# 07-AUDIO_INNER.net
KiCad netlist of a schematic drawn in Altium Designer
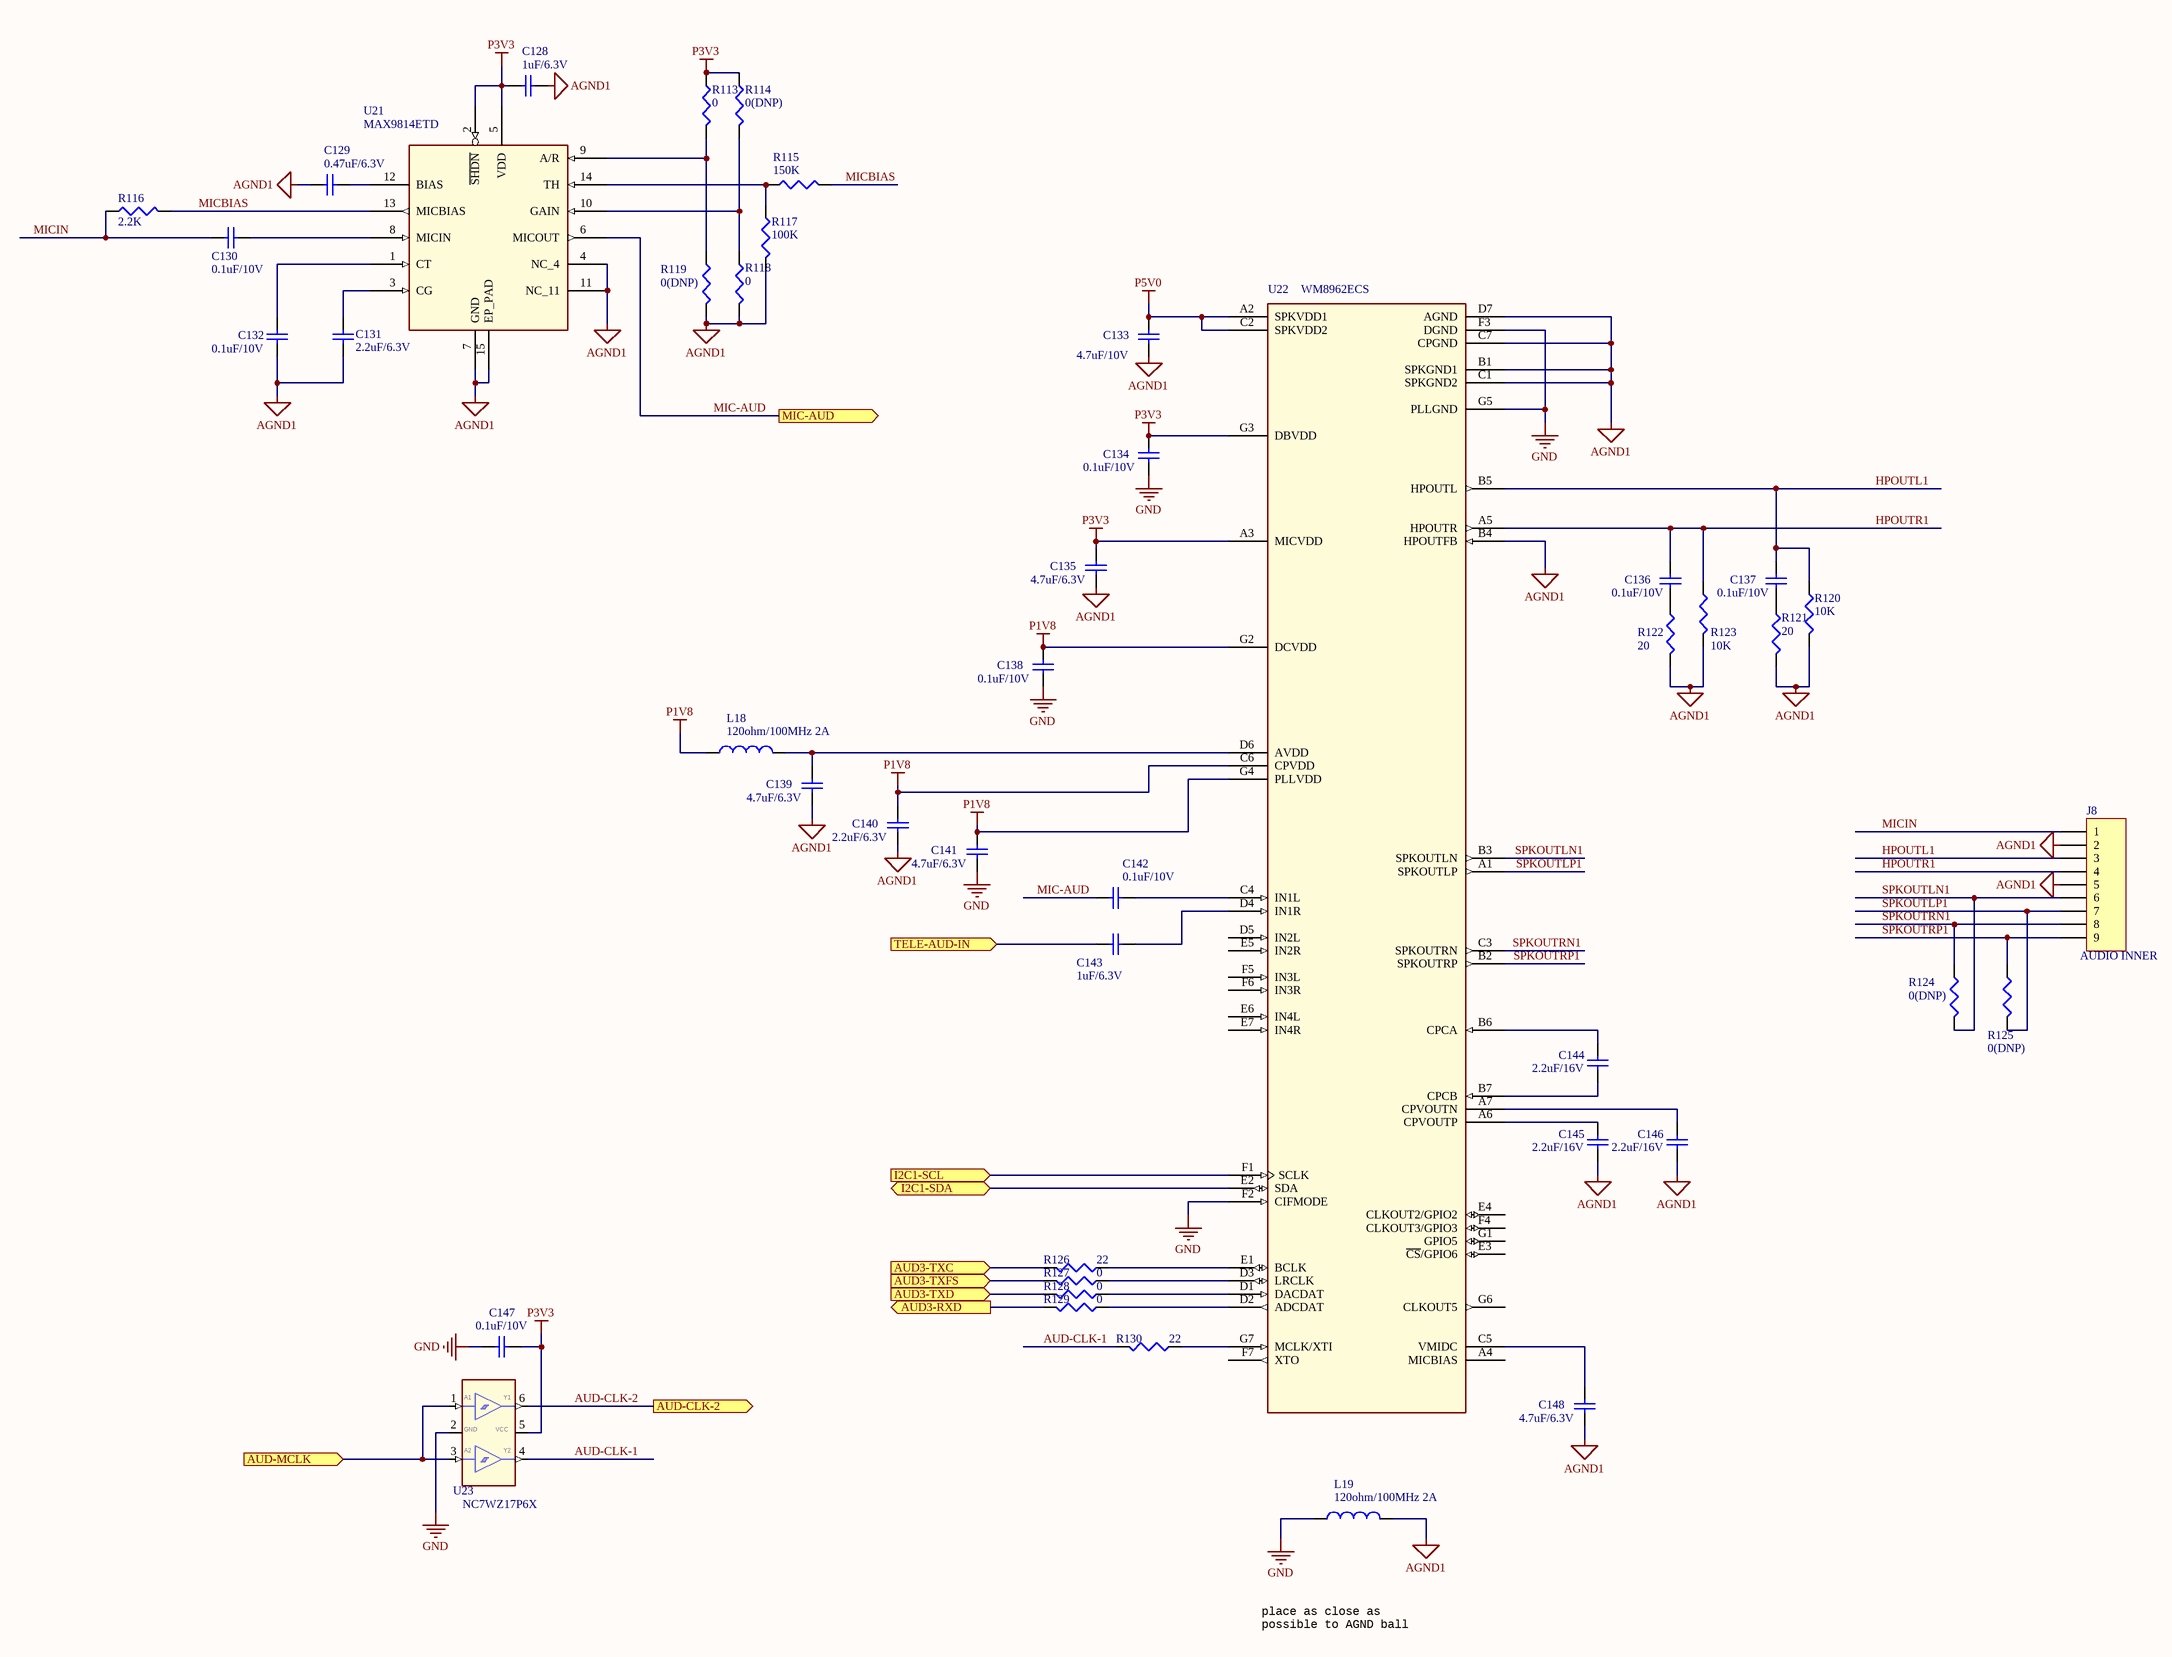
[diagram p0: 07-AUDIO_INNER.SchDoc]

(export (version "E")
  (design (tool "Eeschema 10.0.6"))
  (components
    (comp (ref "C128")
      (value "1uF/6.3V")
      (footprint "0402")
      (description "Capacitor")
      (fields (field (name "PUBLISHER") "Altium Limited"))
      (libsource (lib "Miscellaneous Devices") (part "Cap"))
    )
    (comp (ref "C129")
      (value "0.47uF/6.3V")
      (footprint "0402")
      (description "Capacitor")
      (fields (field (name "PUBLISHER") "Altium Limited"))
      (libsource (lib "Miscellaneous Devices") (part "Cap"))
    )
    (comp (ref "C130")
      (value "0.1uF/10V")
      (footprint "0402")
      (description "Capacitor")
      (fields (field (name "PUBLISHER") "Altium Limited"))
      (libsource (lib "Miscellaneous Devices") (part "Cap"))
    )
    (comp (ref "C131")
      (value "2.2uF/6.3V")
      (footprint "0603")
      (description "Capacitor")
      (fields (field (name "PUBLISHER") "Altium Limited"))
      (libsource (lib "Miscellaneous Devices") (part "Cap"))
    )
    (comp (ref "C132")
      (value "0.1uF/10V")
      (footprint "0402")
      (description "Capacitor")
      (fields (field (name "PUBLISHER") "Altium Limited"))
      (libsource (lib "Miscellaneous Devices") (part "Cap"))
    )
    (comp (ref "C133")
      (value "4.7uF/10V")
      (footprint "0805")
      (description "Capacitor")
      (fields (field (name "PUBLISHER") "Altium Limited"))
      (libsource (lib "Miscellaneous Devices") (part "Cap"))
    )
    (comp (ref "C134")
      (value "0.1uF/10V")
      (footprint "0402")
      (description "Capacitor")
      (fields (field (name "PUBLISHER") "Altium Limited"))
      (libsource (lib "Miscellaneous Devices") (part "Cap"))
    )
    (comp (ref "C135")
      (value "4.7uF/6.3V")
      (footprint "0603")
      (description "Capacitor")
      (fields (field (name "PUBLISHER") "Altium Limited"))
      (libsource (lib "Miscellaneous Devices") (part "Cap"))
    )
    (comp (ref "C136")
      (value "0.1uF/10V")
      (footprint "0402")
      (description "Capacitor")
      (fields (field (name "PUBLISHER") "Altium Limited"))
      (libsource (lib "Miscellaneous Devices") (part "Cap"))
    )
    (comp (ref "C137")
      (value "0.1uF/10V")
      (footprint "0402")
      (description "Capacitor")
      (fields (field (name "PUBLISHER") "Altium Limited"))
      (libsource (lib "Miscellaneous Devices") (part "Cap"))
    )
    (comp (ref "C138")
      (value "0.1uF/10V")
      (footprint "0402")
      (description "Capacitor")
      (fields (field (name "PUBLISHER") "Altium Limited"))
      (libsource (lib "Miscellaneous Devices") (part "Cap"))
    )
    (comp (ref "C139")
      (value "4.7uF/6.3V")
      (footprint "0603")
      (description "Capacitor")
      (fields (field (name "PUBLISHER") "Altium Limited"))
      (libsource (lib "Miscellaneous Devices") (part "Cap"))
    )
    (comp (ref "C140")
      (value "2.2uF/6.3V")
      (footprint "0603")
      (description "Capacitor")
      (fields (field (name "PUBLISHER") "Altium Limited"))
      (libsource (lib "Miscellaneous Devices") (part "Cap"))
    )
    (comp (ref "C141")
      (value "4.7uF/6.3V")
      (footprint "0603")
      (description "Capacitor")
      (fields (field (name "PUBLISHER") "Altium Limited"))
      (libsource (lib "Miscellaneous Devices") (part "Cap"))
    )
    (comp (ref "C142")
      (value "0.1uF/10V")
      (footprint "0402")
      (description "Capacitor")
      (fields (field (name "PUBLISHER") "Altium Limited"))
      (libsource (lib "Miscellaneous Devices") (part "Cap"))
    )
    (comp (ref "C143")
      (value "1uF/6.3V")
      (footprint "0402")
      (description "Capacitor")
      (fields (field (name "PUBLISHER") "Altium Limited"))
      (libsource (lib "Miscellaneous Devices") (part "Cap"))
    )
    (comp (ref "C144")
      (value "2.2uF/16V")
      (footprint "0603")
      (description "Capacitor")
      (fields (field (name "PUBLISHER") "Altium Limited"))
      (libsource (lib "Miscellaneous Devices") (part "Cap"))
    )
    (comp (ref "C145")
      (value "2.2uF/16V")
      (footprint "0603")
      (description "Capacitor")
      (fields (field (name "PUBLISHER") "Altium Limited"))
      (libsource (lib "Miscellaneous Devices") (part "Cap"))
    )
    (comp (ref "C146")
      (value "2.2uF/16V")
      (footprint "0603")
      (description "Capacitor")
      (fields (field (name "PUBLISHER") "Altium Limited"))
      (libsource (lib "Miscellaneous Devices") (part "Cap"))
    )
    (comp (ref "C147")
      (value "0.1uF/10V")
      (footprint "0402")
      (description "Capacitor")
      (fields (field (name "PUBLISHER") "Altium Limited"))
      (libsource (lib "Miscellaneous Devices") (part "Cap"))
    )
    (comp (ref "C148")
      (value "4.7uF/6.3V")
      (footprint "0603")
      (description "Capacitor")
      (fields (field (name "PUBLISHER") "Altium Limited"))
      (libsource (lib "Miscellaneous Devices") (part "Cap"))
    )
    (comp (ref "J8")
      (value "AUDIO INNER")
      (footprint "CON-9PIN")
      (description "Header, 9-Pin")
      (fields (field (name "PUBLISHER") "Altium Limited"))
      (libsource (lib "Miscellaneous Connectors") (part "Header 9"))
    )
    (comp (ref "L18")
      (value "120ohm/100MHz 2A")
      (footprint "0603")
      (description "Inductor")
      (fields (field (name "PUBLISHER") "Altium Limited"))
      (libsource (lib "Miscellaneous Devices") (part "Inductor"))
    )
    (comp (ref "L19")
      (value "120ohm/100MHz 2A")
      (footprint "0603")
      (description "Inductor")
      (fields (field (name "PUBLISHER") "Altium Limited"))
      (libsource (lib "Miscellaneous Devices") (part "Inductor"))
    )
    (comp (ref "R113") (value "0") (footprint "0402") (libsource (lib "*") (part "CR16-1003FM")))
    (comp (ref "R114") (value "0(DNP)") (footprint "0402") (libsource (lib "*") (part "CR16-1003FM")))
    (comp (ref "R115") (value "150K") (footprint "0402") (libsource (lib "*") (part "CR16-1003FM")))
    (comp (ref "R116") (value "2.2K") (footprint "0402") (libsource (lib "*") (part "CR16-1003FM")))
    (comp (ref "R117") (value "100K") (footprint "0402") (libsource (lib "*") (part "CR16-1003FM")))
    (comp (ref "R118") (value "0") (footprint "0402") (libsource (lib "*") (part "CR16-1003FM")))
    (comp (ref "R119") (value "0(DNP)") (footprint "0402") (libsource (lib "*") (part "CR16-1003FM")))
    (comp (ref "R120") (value "10K") (footprint "0402") (libsource (lib "*") (part "CR16-1003FM")))
    (comp (ref "R121") (value "20") (footprint "0402") (libsource (lib "*") (part "CR16-1003FM")))
    (comp (ref "R122") (value "20") (footprint "0402") (libsource (lib "*") (part "CR16-1003FM")))
    (comp (ref "R123") (value "10K") (footprint "0402") (libsource (lib "*") (part "CR16-1003FM")))
    (comp (ref "R124") (value "0(DNP)") (footprint "0603") (libsource (lib "*") (part "CR16-1003FM")))
    (comp (ref "R125") (value "0(DNP)") (footprint "0603") (libsource (lib "*") (part "CR16-1003FM")))
    (comp (ref "R126") (value "22") (footprint "0402") (libsource (lib "*") (part "CR16-1003FM")))
    (comp (ref "R127") (value "0") (footprint "0402") (libsource (lib "*") (part "CR16-1003FM")))
    (comp (ref "R128") (value "0") (footprint "0402") (libsource (lib "*") (part "CR16-1003FM")))
    (comp (ref "R129") (value "0") (footprint "0402") (libsource (lib "*") (part "CR16-1003FM")))
    (comp (ref "R130") (value "22") (footprint "0402") (libsource (lib "*") (part "CR16-1003FM")))
    (comp (ref "U21")
      (value "MAX9814ETD")
      (footprint "TDFN14")
      (description "IC LIN AGC AMP 2.7-5.5V TDFN14")
      (libsource (lib "*") (part "MAX9814_TDFN14"))
    )
    (comp (ref "U22")
      (value "WM8962ECS")
      (footprint "BGA49")
      (description "IC AUDIO CODEC 24BIT DAC 2 CH ADC 1.8V BGA49")
      (libsource (lib "*") (part "WM8962_BGA_49P_CUST"))
    )
    (comp (ref "U23")
      (value "NC7WZ17P6X")
      (footprint "SC70-6")
      (description "IC BUF DUAL SCHMITT 1.65-5.5V SC70-6")
      (libsource (lib "*") (part "NC7WZ17"))
    )
  )
  (nets
    (net (code "1") (name "/AUD-CLK-1") (class "Default")
      (node (ref "R130") (pin "2") (pinfunction "2_2") (pintype "passive"))
      (node (ref "U23") (pin "4") (pinfunction "Y2_4") (pintype "output"))
    )
    (net (code "2") (name "/AUD-CLK-2") (class "Default")
      (node (ref "U23") (pin "6") (pinfunction "Y1_6") (pintype "output"))
    )
    (net (code "3") (name "/AUD-MCLK") (class "Default")
      (node (ref "U23") (pin "1") (pinfunction "A1_1") (pintype "input"))
      (node (ref "U23") (pin "3") (pinfunction "A2_3") (pintype "input"))
    )
    (net (code "4") (name "/AUD3-RXD") (class "Default")
      (node (ref "R129") (pin "2") (pinfunction "2_2") (pintype "passive"))
    )
    (net (code "5") (name "/AUD3-TXC") (class "Default")
      (node (ref "R126") (pin "2") (pinfunction "2_2") (pintype "passive"))
    )
    (net (code "6") (name "/AUD3-TXD") (class "Default")
      (node (ref "R128") (pin "2") (pinfunction "2_2") (pintype "passive"))
    )
    (net (code "7") (name "/AUD3-TXFS") (class "Default")
      (node (ref "R127") (pin "2") (pinfunction "2_2") (pintype "passive"))
    )
    (net (code "8") (name "/HPOUTL1") (class "Default")
      (node (ref "C137") (pin "2") (pinfunction "2_2") (pintype "passive"))
      (node (ref "J8") (pin "3") (pinfunction "3_3") (pintype "passive"))
      (node (ref "R120") (pin "1") (pinfunction "1_1") (pintype "passive"))
      (node (ref "U22") (pin "B5") (pinfunction "HPOUTL_B5") (pintype "output"))
    )
    (net (code "9") (name "/HPOUTR1") (class "Default")
      (node (ref "C136") (pin "2") (pinfunction "2_2") (pintype "passive"))
      (node (ref "J8") (pin "4") (pinfunction "4_4") (pintype "passive"))
      (node (ref "R123") (pin "1") (pinfunction "1_1") (pintype "passive"))
      (node (ref "U22") (pin "A5") (pinfunction "HPOUTR_A5") (pintype "output"))
    )
    (net (code "10") (name "/I2C1-SCL") (class "Default")
      (node (ref "U22") (pin "F1") (pinfunction "SCLK_F1") (pintype "input"))
    )
    (net (code "11") (name "/I2C1-SDA") (class "Default")
      (node (ref "U22") (pin "E2") (pinfunction "SDA_E2") (pintype "bidirectional"))
    )
    (net (code "12") (name "/MIC-AUD") (class "Default")
      (node (ref "C142") (pin "2") (pinfunction "2_2") (pintype "passive"))
      (node (ref "U21") (pin "6") (pinfunction "MICOUT_6") (pintype "output"))
    )
    (net (code "13") (name "/MICBIAS") (class "Default")
      (node (ref "R115") (pin "2") (pinfunction "2_2") (pintype "passive"))
      (node (ref "R116") (pin "2") (pinfunction "2_2") (pintype "passive"))
      (node (ref "U21") (pin "13") (pinfunction "MICBIAS_13") (pintype "output"))
    )
    (net (code "14") (name "/MICIN") (class "Default")
      (node (ref "C130") (pin "2") (pinfunction "2_2") (pintype "passive"))
      (node (ref "J8") (pin "1") (pinfunction "1_1") (pintype "passive"))
      (node (ref "R116") (pin "1") (pinfunction "1_1") (pintype "passive"))
    )
    (net (code "15") (name "/SPKOUTLN1") (class "Default")
      (node (ref "J8") (pin "6") (pinfunction "6_6") (pintype "passive"))
      (node (ref "R124") (pin "2") (pinfunction "2_2") (pintype "passive"))
      (node (ref "U22") (pin "B3") (pinfunction "SPKOUTLN_B3") (pintype "output"))
    )
    (net (code "16") (name "/SPKOUTLP1") (class "Default")
      (node (ref "J8") (pin "7") (pinfunction "7_7") (pintype "passive"))
      (node (ref "R125") (pin "2") (pinfunction "2_2") (pintype "passive"))
      (node (ref "U22") (pin "A1") (pinfunction "SPKOUTLP_A1") (pintype "output"))
    )
    (net (code "17") (name "/SPKOUTRN1") (class "Default")
      (node (ref "J8") (pin "8") (pinfunction "8_8") (pintype "passive"))
      (node (ref "R124") (pin "1") (pinfunction "1_1") (pintype "passive"))
      (node (ref "U22") (pin "C3") (pinfunction "SPKOUTRN_C3") (pintype "output"))
    )
    (net (code "18") (name "/SPKOUTRP1") (class "Default")
      (node (ref "J8") (pin "9") (pinfunction "9_9") (pintype "passive"))
      (node (ref "R125") (pin "1") (pinfunction "1_1") (pintype "passive"))
      (node (ref "U22") (pin "B2") (pinfunction "SPKOUTRP_B2") (pintype "output"))
    )
    (net (code "19") (name "/TELE-AUD-IN") (class "Default")
      (node (ref "C143") (pin "2") (pinfunction "2_2") (pintype "passive"))
    )
    (net (code "20") (name "AGND1") (class "Default")
      (node (ref "C128") (pin "1") (pinfunction "1_1") (pintype "passive"))
      (node (ref "C129") (pin "2") (pinfunction "2_2") (pintype "passive"))
      (node (ref "C131") (pin "2") (pinfunction "2_2") (pintype "passive"))
      (node (ref "C132") (pin "2") (pinfunction "2_2") (pintype "passive"))
      (node (ref "C133") (pin "1") (pinfunction "1_1") (pintype "passive"))
      (node (ref "C135") (pin "1") (pinfunction "1_1") (pintype "passive"))
      (node (ref "C139") (pin "1") (pinfunction "1_1") (pintype "passive"))
      (node (ref "C140") (pin "1") (pinfunction "1_1") (pintype "passive"))
      (node (ref "C145") (pin "1") (pinfunction "1_1") (pintype "passive"))
      (node (ref "C146") (pin "1") (pinfunction "1_1") (pintype "passive"))
      (node (ref "C148") (pin "1") (pinfunction "1_1") (pintype "passive"))
      (node (ref "J8") (pin "2") (pinfunction "2_2") (pintype "passive"))
      (node (ref "J8") (pin "5") (pinfunction "5_5") (pintype "passive"))
      (node (ref "L19") (pin "2") (pinfunction "2_2") (pintype "passive"))
      (node (ref "R117") (pin "2") (pinfunction "2_2") (pintype "passive"))
      (node (ref "R118") (pin "2") (pinfunction "2_2") (pintype "passive"))
      (node (ref "R119") (pin "2") (pinfunction "2_2") (pintype "passive"))
      (node (ref "R120") (pin "2") (pinfunction "2_2") (pintype "passive"))
      (node (ref "R121") (pin "2") (pinfunction "2_2") (pintype "passive"))
      (node (ref "R122") (pin "2") (pinfunction "2_2") (pintype "passive"))
      (node (ref "R123") (pin "2") (pinfunction "2_2") (pintype "passive"))
      (node (ref "U21") (pin "11") (pinfunction "NC_11_11") (pintype "passive"))
      (node (ref "U21") (pin "15") (pinfunction "EP_PAD_15") (pintype "power_in"))
      (node (ref "U21") (pin "4") (pinfunction "NC_4_4") (pintype "passive"))
      (node (ref "U21") (pin "7") (pinfunction "GND_7") (pintype "power_in"))
      (node (ref "U22") (pin "B1") (pinfunction "SPKGND1_B1") (pintype "power_in"))
      (node (ref "U22") (pin "B4") (pinfunction "HPOUTFB_B4") (pintype "input"))
      (node (ref "U22") (pin "C1") (pinfunction "SPKGND2_C1") (pintype "power_in"))
      (node (ref "U22") (pin "C7") (pinfunction "CPGND_C7") (pintype "power_in"))
      (node (ref "U22") (pin "D7") (pinfunction "AGND_D7") (pintype "power_in"))
    )
    (net (code "21") (name "GND") (class "Default")
      (node (ref "C134") (pin "1") (pinfunction "1_1") (pintype "passive"))
      (node (ref "C138") (pin "1") (pinfunction "1_1") (pintype "passive"))
      (node (ref "C141") (pin "1") (pinfunction "1_1") (pintype "passive"))
      (node (ref "C147") (pin "2") (pinfunction "2_2") (pintype "passive"))
      (node (ref "L19") (pin "1") (pinfunction "1_1") (pintype "passive"))
      (node (ref "U22") (pin "F2") (pinfunction "CIFMODE_F2") (pintype "input"))
      (node (ref "U22") (pin "F3") (pinfunction "DGND_F3") (pintype "power_in"))
      (node (ref "U22") (pin "G5") (pinfunction "PLLGND_G5") (pintype "power_in"))
      (node (ref "U23") (pin "2") (pinfunction "GND_2") (pintype "power_in"))
    )
    (net (code "22") (name "Net-(C136-Pad1)") (class "Default")
      (node (ref "C136") (pin "1") (pinfunction "1_1") (pintype "passive"))
      (node (ref "R122") (pin "1") (pinfunction "1_1") (pintype "passive"))
    )
    (net (code "23") (name "Net-(C137-Pad1)") (class "Default")
      (node (ref "C137") (pin "1") (pinfunction "1_1") (pintype "passive"))
      (node (ref "R121") (pin "1") (pinfunction "1_1") (pintype "passive"))
    )
    (net (code "24") (name "Net-(U21-A{slash}R)") (class "Default")
      (node (ref "R113") (pin "2") (pinfunction "2_2") (pintype "passive"))
      (node (ref "R119") (pin "1") (pinfunction "1_1") (pintype "passive"))
      (node (ref "U21") (pin "9") (pinfunction "A/R_9") (pintype "input"))
    )
    (net (code "25") (name "Net-(U21-BIAS)") (class "Default")
      (node (ref "C129") (pin "1") (pinfunction "1_1") (pintype "passive"))
      (node (ref "U21") (pin "12") (pinfunction "BIAS_12") (pintype "power_in"))
    )
    (net (code "26") (name "Net-(U21-CG)") (class "Default")
      (node (ref "C131") (pin "1") (pinfunction "1_1") (pintype "passive"))
      (node (ref "U21") (pin "3") (pinfunction "CG_3") (pintype "input"))
    )
    (net (code "27") (name "Net-(U21-CT)") (class "Default")
      (node (ref "C132") (pin "1") (pinfunction "1_1") (pintype "passive"))
      (node (ref "U21") (pin "1") (pinfunction "CT_1") (pintype "input"))
    )
    (net (code "28") (name "Net-(U21-GAIN)") (class "Default")
      (node (ref "R114") (pin "2") (pinfunction "2_2") (pintype "passive"))
      (node (ref "R118") (pin "1") (pinfunction "1_1") (pintype "passive"))
      (node (ref "U21") (pin "10") (pinfunction "GAIN_10") (pintype "input"))
    )
    (net (code "29") (name "Net-(U21-MICIN)") (class "Default")
      (node (ref "C130") (pin "1") (pinfunction "1_1") (pintype "passive"))
      (node (ref "U21") (pin "8") (pinfunction "MICIN_8") (pintype "input"))
    )
    (net (code "30") (name "Net-(U21-TH)") (class "Default")
      (node (ref "R115") (pin "1") (pinfunction "1_1") (pintype "passive"))
      (node (ref "R117") (pin "1") (pinfunction "1_1") (pintype "passive"))
      (node (ref "U21") (pin "14") (pinfunction "TH_14") (pintype "input"))
    )
    (net (code "31") (name "Net-(U22-ADCDAT)") (class "Default")
      (node (ref "R129") (pin "1") (pinfunction "1_1") (pintype "passive"))
      (node (ref "U22") (pin "D2") (pinfunction "ADCDAT_D2") (pintype "output"))
    )
    (net (code "32") (name "Net-(U22-AVDD)") (class "Default")
      (node (ref "C139") (pin "2") (pinfunction "2_2") (pintype "passive"))
      (node (ref "L18") (pin "2") (pinfunction "2_2") (pintype "passive"))
      (node (ref "U22") (pin "D6") (pinfunction "AVDD_D6") (pintype "power_in"))
    )
    (net (code "33") (name "Net-(U22-BCLK)") (class "Default")
      (node (ref "R126") (pin "1") (pinfunction "1_1") (pintype "passive"))
      (node (ref "U22") (pin "E1") (pinfunction "BCLK_E1") (pintype "bidirectional"))
    )
    (net (code "34") (name "Net-(U22-CPCA)") (class "Default")
      (node (ref "C144") (pin "2") (pinfunction "2_2") (pintype "passive"))
      (node (ref "U22") (pin "B6") (pinfunction "CPCA_B6") (pintype "input"))
    )
    (net (code "35") (name "Net-(U22-CPCB)") (class "Default")
      (node (ref "C144") (pin "1") (pinfunction "1_1") (pintype "passive"))
      (node (ref "U22") (pin "B7") (pinfunction "CPCB_B7") (pintype "input"))
    )
    (net (code "36") (name "Net-(U22-CPVOUTN)") (class "Default")
      (node (ref "C146") (pin "2") (pinfunction "2_2") (pintype "passive"))
      (node (ref "U22") (pin "A7") (pinfunction "CPVOUTN_A7") (pintype "power_in"))
    )
    (net (code "37") (name "Net-(U22-CPVOUTP)") (class "Default")
      (node (ref "C145") (pin "2") (pinfunction "2_2") (pintype "passive"))
      (node (ref "U22") (pin "A6") (pinfunction "CPVOUTP_A6") (pintype "power_in"))
    )
    (net (code "38") (name "Net-(U22-DACDAT)") (class "Default")
      (node (ref "R128") (pin "1") (pinfunction "1_1") (pintype "passive"))
      (node (ref "U22") (pin "D1") (pinfunction "DACDAT_D1") (pintype "input"))
    )
    (net (code "39") (name "Net-(U22-IN1L)") (class "Default")
      (node (ref "C142") (pin "1") (pinfunction "1_1") (pintype "passive"))
      (node (ref "U22") (pin "C4") (pinfunction "IN1L_C4") (pintype "input"))
    )
    (net (code "40") (name "Net-(U22-IN1R)") (class "Default")
      (node (ref "C143") (pin "1") (pinfunction "1_1") (pintype "passive"))
      (node (ref "U22") (pin "D4") (pinfunction "IN1R_D4") (pintype "input"))
    )
    (net (code "41") (name "Net-(U22-LRCLK)") (class "Default")
      (node (ref "R127") (pin "1") (pinfunction "1_1") (pintype "passive"))
      (node (ref "U22") (pin "D3") (pinfunction "LRCLK_D3") (pintype "bidirectional"))
    )
    (net (code "42") (name "Net-(U22-MCLK{slash}XTI)") (class "Default")
      (node (ref "R130") (pin "1") (pinfunction "1_1") (pintype "passive"))
      (node (ref "U22") (pin "G7") (pinfunction "MCLK/XTI_G7") (pintype "input"))
    )
    (net (code "43") (name "Net-(U22-VMIDC)") (class "Default")
      (node (ref "C148") (pin "2") (pinfunction "2_2") (pintype "passive"))
      (node (ref "U22") (pin "C5") (pinfunction "VMIDC_C5") (pintype "power_in"))
    )
    (net (code "44") (name "P1V8") (class "Default")
      (node (ref "C138") (pin "2") (pinfunction "2_2") (pintype "passive"))
      (node (ref "C140") (pin "2") (pinfunction "2_2") (pintype "passive"))
      (node (ref "C141") (pin "2") (pinfunction "2_2") (pintype "passive"))
      (node (ref "L18") (pin "1") (pinfunction "1_1") (pintype "passive"))
      (node (ref "U22") (pin "C6") (pinfunction "CPVDD_C6") (pintype "power_in"))
      (node (ref "U22") (pin "G2") (pinfunction "DCVDD_G2") (pintype "power_in"))
      (node (ref "U22") (pin "G4") (pinfunction "PLLVDD_G4") (pintype "power_in"))
    )
    (net (code "45") (name "P3V3") (class "Default")
      (node (ref "C128") (pin "2") (pinfunction "2_2") (pintype "passive"))
      (node (ref "C134") (pin "2") (pinfunction "2_2") (pintype "passive"))
      (node (ref "C135") (pin "2") (pinfunction "2_2") (pintype "passive"))
      (node (ref "C147") (pin "1") (pinfunction "1_1") (pintype "passive"))
      (node (ref "R113") (pin "1") (pinfunction "1_1") (pintype "passive"))
      (node (ref "R114") (pin "1") (pinfunction "1_1") (pintype "passive"))
      (node (ref "U21") (pin "2") (pinfunction "~{SHDN}_2") (pintype "input"))
      (node (ref "U21") (pin "5") (pinfunction "VDD_5") (pintype "power_in"))
      (node (ref "U22") (pin "A3") (pinfunction "MICVDD_A3") (pintype "power_in"))
      (node (ref "U22") (pin "G3") (pinfunction "DBVDD_G3") (pintype "power_in"))
      (node (ref "U23") (pin "5") (pinfunction "VCC_5") (pintype "power_in"))
    )
    (net (code "46") (name "P5V0") (class "Default")
      (node (ref "C133") (pin "2") (pinfunction "2_2") (pintype "passive"))
      (node (ref "U22") (pin "A2") (pinfunction "SPKVDD1_A2") (pintype "power_in"))
      (node (ref "U22") (pin "C2") (pinfunction "SPKVDD2_C2") (pintype "power_in"))
    )
    (net (code "47") (name "unconnected-(U22-CLKOUT2{slash}GPIO2-PadE4)") (class "Default")
      (node (ref "U22") (pin "E4") (pinfunction "CLKOUT2/GPIO2_E4") (pintype "bidirectional"))
    )
    (net (code "48") (name "unconnected-(U22-CLKOUT3{slash}GPIO3-PadF4)") (class "Default")
      (node (ref "U22") (pin "F4") (pinfunction "CLKOUT3/GPIO3_F4") (pintype "bidirectional"))
    )
    (net (code "49") (name "unconnected-(U22-CLKOUT5-PadG6)") (class "Default")
      (node (ref "U22") (pin "G6") (pinfunction "CLKOUT5_G6") (pintype "output"))
    )
    (net (code "50") (name "unconnected-(U22-GPIO5-PadG1)") (class "Default")
      (node (ref "U22") (pin "G1") (pinfunction "GPIO5_G1") (pintype "bidirectional"))
    )
    (net (code "51") (name "unconnected-(U22-IN2L-PadD5)") (class "Default")
      (node (ref "U22") (pin "D5") (pinfunction "IN2L_D5") (pintype "input"))
    )
    (net (code "52") (name "unconnected-(U22-IN2R-PadE5)") (class "Default")
      (node (ref "U22") (pin "E5") (pinfunction "IN2R_E5") (pintype "input"))
    )
    (net (code "53") (name "unconnected-(U22-IN3L-PadF5)") (class "Default")
      (node (ref "U22") (pin "F5") (pinfunction "IN3L_F5") (pintype "input"))
    )
    (net (code "54") (name "unconnected-(U22-IN3R-PadF6)") (class "Default")
      (node (ref "U22") (pin "F6") (pinfunction "IN3R_F6") (pintype "input"))
    )
    (net (code "55") (name "unconnected-(U22-IN4L-PadE6)") (class "Default")
      (node (ref "U22") (pin "E6") (pinfunction "IN4L_E6") (pintype "input"))
    )
    (net (code "56") (name "unconnected-(U22-IN4R-PadE7)") (class "Default")
      (node (ref "U22") (pin "E7") (pinfunction "IN4R_E7") (pintype "input"))
    )
    (net (code "57") (name "unconnected-(U22-MICBIAS-PadA4)") (class "Default")
      (node (ref "U22") (pin "A4") (pinfunction "MICBIAS_A4") (pintype "passive"))
    )
    (net (code "58") (name "unconnected-(U22-XTO-PadF7)") (class "Default")
      (node (ref "U22") (pin "F7") (pinfunction "XTO_F7") (pintype "output"))
    )
    (net (code "59") (name "unconnected-(U22-~{CS}{slash}GPIO6-PadE3)") (class "Default")
      (node (ref "U22") (pin "E3") (pinfunction "~{CS}/GPIO6_E3") (pintype "bidirectional"))
    )
  )
)
